# SCH_aqMood_2025-03-14.net
KiCad netlist of a schematic drawn in EasyEDA
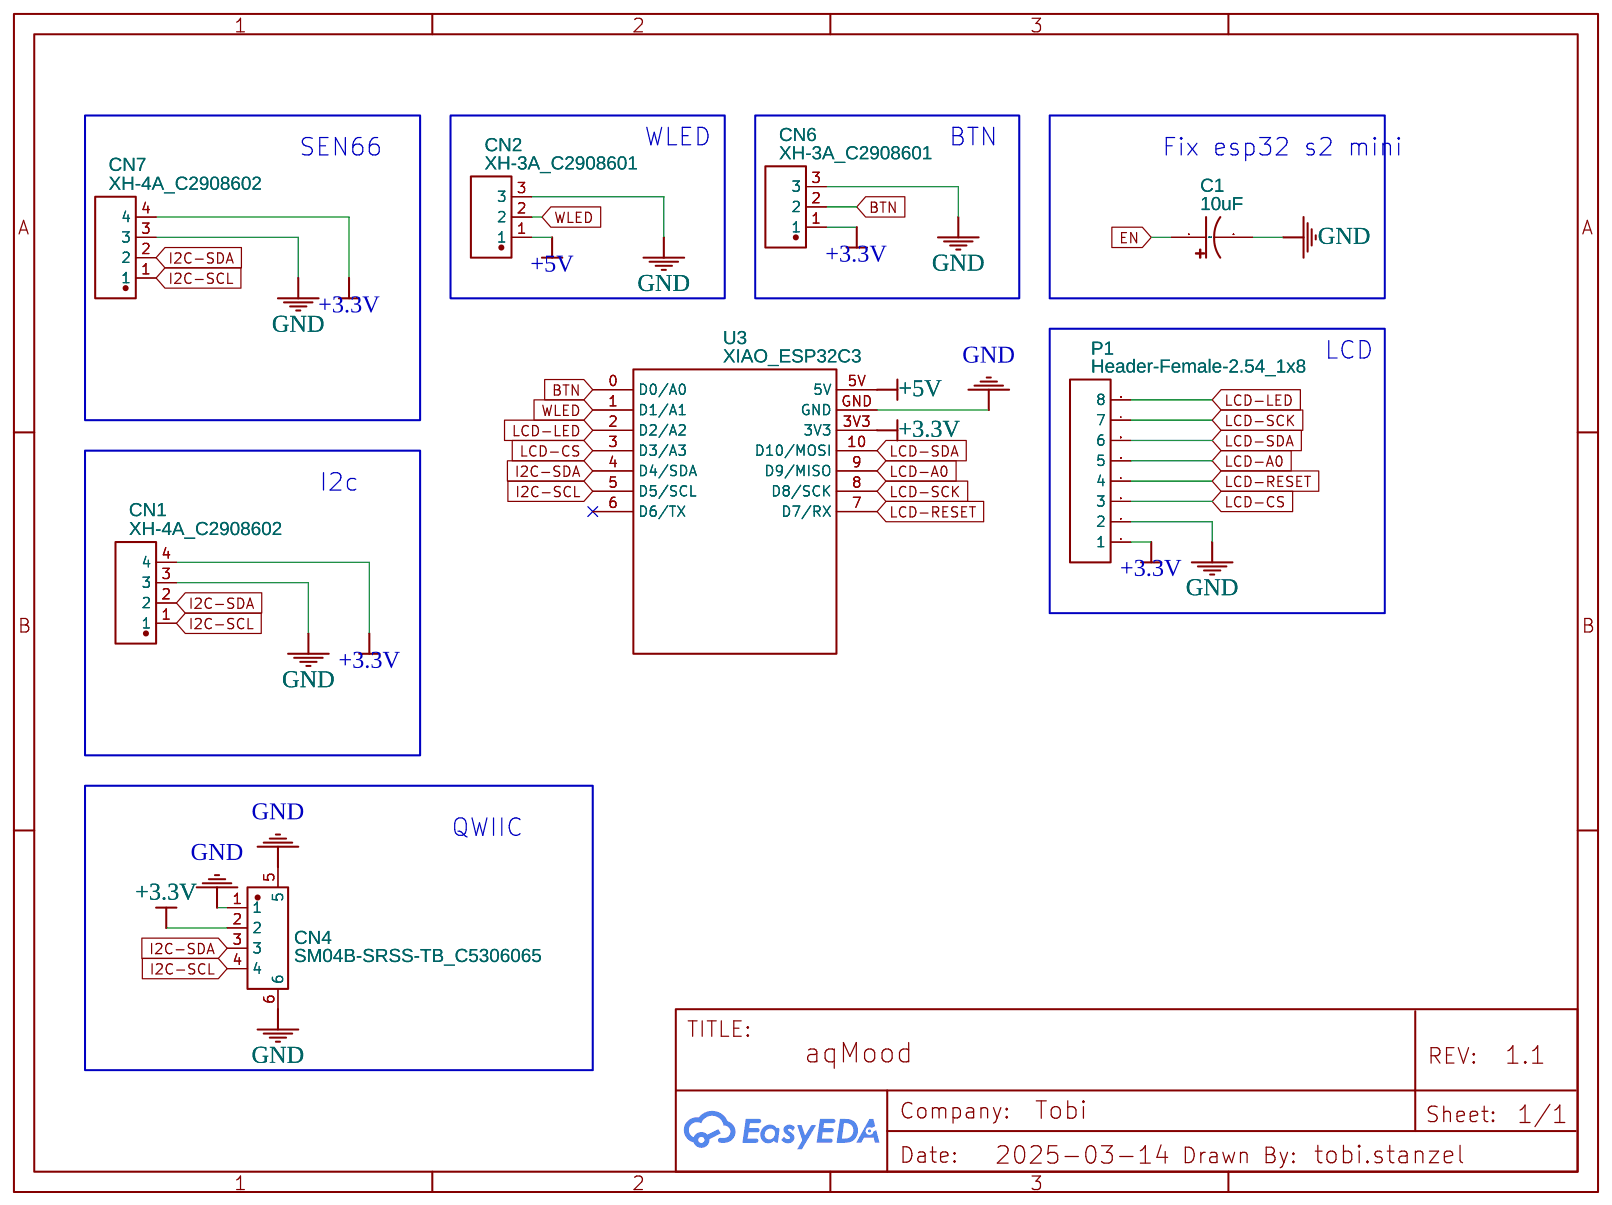
[diagram p0: schematic sheet]

(export (version "E")
  (design (tool "Eeschema 10.0.6"))
  (components
    (comp (ref "C1")
      (value "10uF")
      (fields
        (field (name "Manufacturer Part") "ECR1HGK100MFA050011")
        (field (name "Manufacturer") "Jianghai(南通江海)")
      )
      (libsource (lib "") (part "ECR1HGK100MFA050011"))
    )
    (comp (ref "CN1")
      (value "XH-4A_C2908602")
      (fields (field (name "Manufacturer Part") "XH-4A") (field (name "Manufacturer") "HCTL(华灿天禄)"))
      (libsource (lib "") (part "XH-4A_C2908602"))
    )
    (comp (ref "CN2")
      (value "XH-3A_C2908601")
      (fields (field (name "Manufacturer Part") "XH-3A") (field (name "Manufacturer") "HCTL(华灿天禄)"))
      (libsource (lib "") (part "XH-3A_C2908601"))
    )
    (comp (ref "CN4")
      (value "SM04B-SRSS-TB_C5306065")
      (fields (field (name "Manufacturer Part") "SM04B-SRSS-TB"))
      (libsource (lib "") (part "SM04B-SRSS-TB_C5306065"))
    )
    (comp (ref "CN6")
      (value "XH-3A_C2908601")
      (fields (field (name "Manufacturer Part") "XH-3A") (field (name "Manufacturer") "HCTL(华灿天禄)"))
      (libsource (lib "") (part "XH-3A_C2908601"))
    )
    (comp (ref "CN7")
      (value "XH-4A_C2908602")
      (fields (field (name "Manufacturer Part") "XH-4A") (field (name "Manufacturer") "HCTL(华灿天禄)"))
      (libsource (lib "") (part "XH-4A_C2908602"))
    )
    (comp (ref "P1")
      (value "Header-Female-2.54_1x8")
      (fields (field (name "Manufacturer Part") "2.54-1*8P母环保") (field (name "Manufacturer") "BOOMELE(博穆精密)"))
      (libsource (lib "") (part "Header-Female-2.54_1x8"))
    )
    (comp (ref "U3")
      (value "XIAO_ESP32C3")
      (fields (field (name "Manufacturer Part") "XIAO ESP32C3") (field (name "Manufacturer") "SeeedStudio"))
      (libsource (lib "") (part "XIAO_ESP32C3"))
    )
  )
  (nets
    (net (code "1") (name "+3.3V") (class "Default")
      (node (ref "CN1") (pin "4") (pinfunction "4_4") (pintype "unspecified"))
      (node (ref "CN4") (pin "2") (pinfunction "2_2") (pintype "unspecified"))
      (node (ref "CN6") (pin "1") (pinfunction "1_1") (pintype "unspecified"))
      (node (ref "CN7") (pin "4") (pinfunction "4_4") (pintype "unspecified"))
      (node (ref "P1") (pin "1") (pinfunction "1_1") (pintype "input"))
      (node (ref "U3") (pin "3V3") (pinfunction "3V3_3V3") (pintype "unspecified"))
    )
    (net (code "2") (name "+5V") (class "Default")
      (node (ref "CN2") (pin "1") (pinfunction "1_1") (pintype "unspecified"))
      (node (ref "U3") (pin "5V") (pinfunction "5V_5V") (pintype "unspecified"))
    )
    (net (code "3") (name "BTN") (class "Default")
      (node (ref "CN6") (pin "2") (pinfunction "2_2") (pintype "unspecified"))
      (node (ref "U3") (pin "0") (pinfunction "D0/A0_0") (pintype "unspecified"))
    )
    (net (code "4") (name "EN") (class "Default")
      (node (ref "C1") (pin "1") (pinfunction "1_1") (pintype "unspecified"))
    )
    (net (code "5") (name "GND") (class "Default")
      (node (ref "C1") (pin "2") (pinfunction "2_2") (pintype "unspecified"))
      (node (ref "CN1") (pin "3") (pinfunction "3_3") (pintype "unspecified"))
      (node (ref "CN2") (pin "3") (pinfunction "3_3") (pintype "unspecified"))
      (node (ref "CN4") (pin "1") (pinfunction "1_1") (pintype "unspecified"))
      (node (ref "CN4") (pin "5") (pinfunction "5_5") (pintype "unspecified"))
      (node (ref "CN4") (pin "6") (pinfunction "6_6") (pintype "unspecified"))
      (node (ref "CN6") (pin "3") (pinfunction "3_3") (pintype "unspecified"))
      (node (ref "CN7") (pin "3") (pinfunction "3_3") (pintype "unspecified"))
      (node (ref "P1") (pin "2") (pinfunction "2_2") (pintype "input"))
      (node (ref "U3") (pin "GND") (pinfunction "GND_GND") (pintype "unspecified"))
    )
    (net (code "6") (name "I2C-SCL") (class "Default")
      (node (ref "CN1") (pin "1") (pinfunction "1_1") (pintype "unspecified"))
      (node (ref "CN4") (pin "4") (pinfunction "4_4") (pintype "unspecified"))
      (node (ref "CN7") (pin "1") (pinfunction "1_1") (pintype "unspecified"))
      (node (ref "U3") (pin "5") (pinfunction "D5/SCL_5") (pintype "unspecified"))
    )
    (net (code "7") (name "I2C-SDA") (class "Default")
      (node (ref "CN1") (pin "2") (pinfunction "2_2") (pintype "unspecified"))
      (node (ref "CN4") (pin "3") (pinfunction "3_3") (pintype "unspecified"))
      (node (ref "CN7") (pin "2") (pinfunction "2_2") (pintype "unspecified"))
      (node (ref "U3") (pin "4") (pinfunction "D4/SDA_4") (pintype "unspecified"))
    )
    (net (code "8") (name "LCD-A0") (class "Default")
      (node (ref "P1") (pin "5") (pinfunction "5_5") (pintype "input"))
      (node (ref "U3") (pin "9") (pinfunction "D9/MISO_9") (pintype "unspecified"))
    )
    (net (code "9") (name "LCD-CS") (class "Default")
      (node (ref "P1") (pin "3") (pinfunction "3_3") (pintype "input"))
      (node (ref "U3") (pin "3") (pinfunction "D3/A3_3") (pintype "unspecified"))
    )
    (net (code "10") (name "LCD-LED") (class "Default")
      (node (ref "P1") (pin "8") (pinfunction "8_8") (pintype "input"))
      (node (ref "U3") (pin "2") (pinfunction "D2/A2_2") (pintype "unspecified"))
    )
    (net (code "11") (name "LCD-RESET") (class "Default")
      (node (ref "P1") (pin "4") (pinfunction "4_4") (pintype "input"))
      (node (ref "U3") (pin "7") (pinfunction "D7/RX_7") (pintype "unspecified"))
    )
    (net (code "12") (name "LCD-SCK") (class "Default")
      (node (ref "P1") (pin "7") (pinfunction "7_7") (pintype "input"))
      (node (ref "U3") (pin "8") (pinfunction "D8/SCK_8") (pintype "unspecified"))
    )
    (net (code "13") (name "LCD-SDA") (class "Default")
      (node (ref "P1") (pin "6") (pinfunction "6_6") (pintype "input"))
      (node (ref "U3") (pin "10") (pinfunction "D10/MOSI_10") (pintype "unspecified"))
    )
    (net (code "14") (name "WLED") (class "Default")
      (node (ref "CN2") (pin "2") (pinfunction "2_2") (pintype "unspecified"))
      (node (ref "U3") (pin "1") (pinfunction "D1/A1_1") (pintype "unspecified"))
    )
    (net (code "15") (name "unconnected-(U3-D6{slash}TX-Pad6)") (class "Default")
      (node (ref "U3") (pin "6") (pinfunction "D6/TX_6") (pintype "unspecified+no_connect"))
    )
  )
)
